# image_reject.net
KiCad netlist of a schematic drawn in Altium Designer
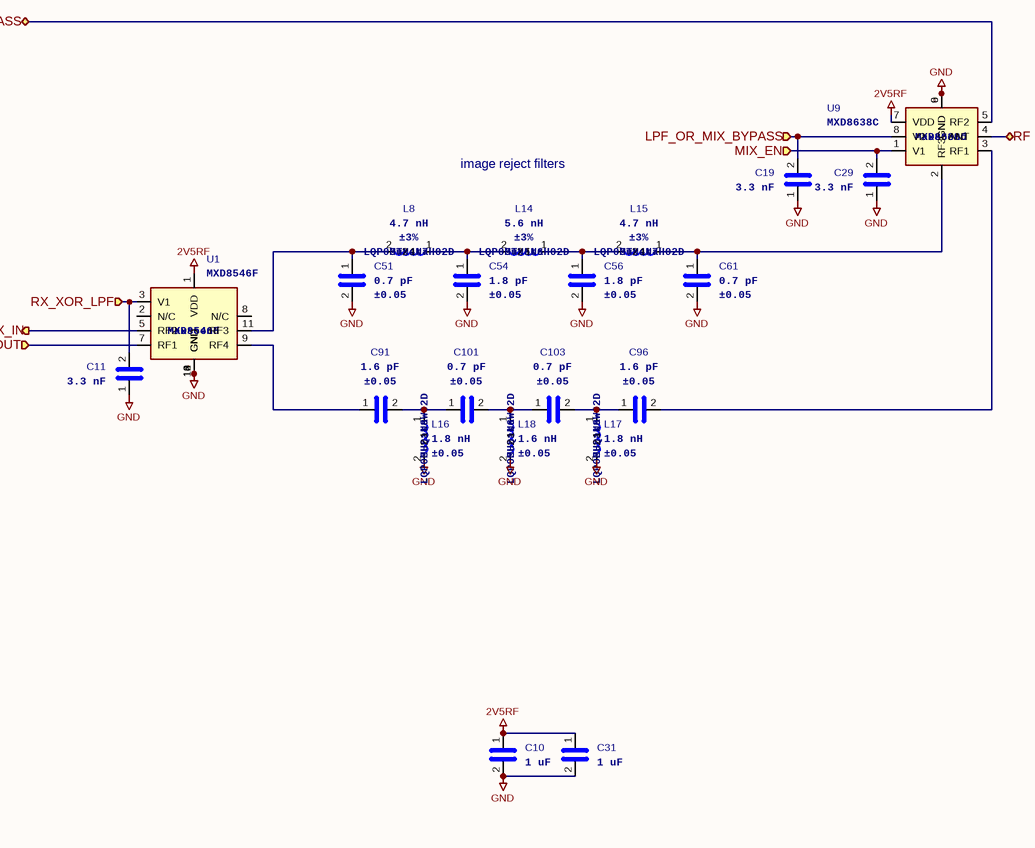
[diagram p0: image_reject.SchDoc]

(export (version "E")
  (design (tool "Eeschema 10.0.6"))
  (components
    (comp (ref "C10")
      (value "1 uF")
      (footprint "C_0201_0603Metric")
      (fields (field (name "MANUFACTURER") "Murata") (field (name "PART NUMBER") "GRM033R61A105ME44D"))
      (libsource (lib "Device") (part "C"))
    )
    (comp (ref "C11")
      (value "3.3 nF")
      (footprint "C_0201_0603Metric")
      (fields (field (name "MANUFACTURER") "Murata") (field (name "PART NUMBER") "GRM033R71A332KA01D"))
      (libsource (lib "Device") (part "C"))
    )
    (comp (ref "C19")
      (value "3.3 nF")
      (footprint "C_0201_0603Metric")
      (fields (field (name "MANUFACTURER") "Murata") (field (name "PART NUMBER") "GRM033R71A332KA01D"))
      (libsource (lib "Device") (part "C"))
    )
    (comp (ref "C29")
      (value "3.3 nF")
      (footprint "C_0201_0603Metric")
      (fields (field (name "MANUFACTURER") "Murata") (field (name "PART NUMBER") "GRM033R71A332KA01D"))
      (libsource (lib "Device") (part "C"))
    )
    (comp (ref "C31")
      (value "1 uF")
      (footprint "C_0201_0603Metric")
      (fields (field (name "MANUFACTURER") "Murata") (field (name "PART NUMBER") "GRM033R61A105ME44D"))
      (libsource (lib "Device") (part "C"))
    )
    (comp (ref "C51")
      (value "0.7 pF")
      (footprint "C_0201_0603Metric")
      (fields
        (field (name "MANUFACTURER") "Murata")
        (field (name "PART NUMBER") "GRM0335C1ER70WA01D")
        (field (name "TOLERANCE") "±0.05")
      )
      (libsource (lib "Device") (part "C"))
    )
    (comp (ref "C54")
      (value "1.8 pF")
      (footprint "C_0201_0603Metric")
      (fields
        (field (name "MANUFACTURER") "Murata")
        (field (name "PART NUMBER") "GRM0335C1E1R8WA01D")
        (field (name "TOLERANCE") "±0.05")
      )
      (libsource (lib "Device") (part "C"))
    )
    (comp (ref "C56")
      (value "1.8 pF")
      (footprint "C_0201_0603Metric")
      (fields
        (field (name "MANUFACTURER") "Murata")
        (field (name "PART NUMBER") "GRM0335C1E1R8WA01D")
        (field (name "TOLERANCE") "±0.05")
      )
      (libsource (lib "Device") (part "C"))
    )
    (comp (ref "C61")
      (value "0.7 pF")
      (footprint "C_0201_0603Metric")
      (fields
        (field (name "MANUFACTURER") "Murata")
        (field (name "PART NUMBER") "GRM0335C1ER70WA01D")
        (field (name "TOLERANCE") "±0.05")
      )
      (libsource (lib "Device") (part "C"))
    )
    (comp (ref "C91")
      (value "1.6 pF")
      (footprint "C_0201_0603Metric")
      (fields
        (field (name "MANUFACTURER") "Murata")
        (field (name "PART NUMBER") "GRM0335C1E1R6WA01D")
        (field (name "TOLERANCE") "±0.05")
      )
      (libsource (lib "Device") (part "C"))
    )
    (comp (ref "C96")
      (value "1.6 pF")
      (footprint "C_0201_0603Metric")
      (fields
        (field (name "MANUFACTURER") "Murata")
        (field (name "PART NUMBER") "GRM0335C1E1R6WA01D")
        (field (name "TOLERANCE") "±0.05")
      )
      (libsource (lib "Device") (part "C"))
    )
    (comp (ref "C101")
      (value "0.7 pF")
      (footprint "C_0201_0603Metric")
      (fields
        (field (name "MANUFACTURER") "Murata")
        (field (name "PART NUMBER") "GRM0335C1ER70WA01D")
        (field (name "TOLERANCE") "±0.05")
      )
      (libsource (lib "Device") (part "C"))
    )
    (comp (ref "C103")
      (value "0.7 pF")
      (footprint "C_0201_0603Metric")
      (fields
        (field (name "MANUFACTURER") "Murata")
        (field (name "PART NUMBER") "GRM0335C1ER70WA01D")
        (field (name "TOLERANCE") "±0.05")
      )
      (libsource (lib "Device") (part "C"))
    )
    (comp (ref "L8")
      (value "4.7 nH")
      (footprint "L_0201_0603Metric")
      (fields
        (field (name "MANUFACTURER") "Murata")
        (field (name "PART NUMBER") "LQP03TN4N7H02D")
        (field (name "TOLERANCE") "±3%")
      )
      (libsource (lib "Device") (part "L"))
    )
    (comp (ref "L14")
      (value "5.6 nH")
      (footprint "L_0201_0603Metric")
      (fields
        (field (name "MANUFACTURER") "Murata")
        (field (name "PART NUMBER") "LQP03TN5N6H02D")
        (field (name "TOLERANCE") "±3%")
      )
      (libsource (lib "Device") (part "L"))
    )
    (comp (ref "L15")
      (value "4.7 nH")
      (footprint "L_0201_0603Metric")
      (fields
        (field (name "MANUFACTURER") "Murata")
        (field (name "PART NUMBER") "LQP03TN4N7H02D")
        (field (name "TOLERANCE") "±3%")
      )
      (libsource (lib "Device") (part "L"))
    )
    (comp (ref "L16")
      (value "1.8 nH")
      (footprint "L_0201_0603Metric")
      (fields
        (field (name "MANUFACTURER") "Murata")
        (field (name "PART NUMBER") "LQP03HQ1N8W02D")
        (field (name "TOLERANCE") "±0.05")
      )
      (libsource (lib "Device") (part "L"))
    )
    (comp (ref "L17")
      (value "1.8 nH")
      (footprint "L_0201_0603Metric")
      (fields
        (field (name "MANUFACTURER") "Murata")
        (field (name "PART NUMBER") "LQP03HQ1N8W02D")
        (field (name "TOLERANCE") "±0.05")
      )
      (libsource (lib "Device") (part "L"))
    )
    (comp (ref "L18")
      (value "1.6 nH")
      (footprint "L_0201_0603Metric")
      (fields
        (field (name "MANUFACTURER") "Murata")
        (field (name "PART NUMBER") "LQP03HQ1N6W02D")
        (field (name "TOLERANCE") "±0.05")
      )
      (libsource (lib "Device") (part "L"))
    )
    (comp (ref "U1")
      (value "MXD8546F")
      (footprint "QFN-12-1EP_2x2mm_P0.5mm_EP1x1mm")
      (fields (field (name "MANUFACTURER") "Maxscend") (field (name "PART NUMBER") "MXD8546F"))
      (libsource (lib "praline") (part "MXD8546F"))
    )
    (comp (ref "U9")
      (value "MXD8638C")
      (footprint "MXD8638C")
      (fields (field (name "MANUFACTURER") "Maxscend") (field (name "PART NUMBER") "MXD8638C"))
      (libsource (lib "praline") (part "MXD8638"))
    )
  )
  (nets
    (net (code "1") (name "/LPF_OR_MIX_BYPASS") (class "Default")
      (node (ref "C19") (pin "2") (pinfunction "2_2") (pintype "passive"))
      (node (ref "U9") (pin "8") (pinfunction "V2_8") (pintype "passive"))
    )
    (net (code "2") (name "/MIX_BYPASS") (class "Default")
      (node (ref "U9") (pin "5") (pinfunction "RF2_5") (pintype "passive"))
    )
    (net (code "3") (name "/MIX_EN") (class "Default")
      (node (ref "C29") (pin "2") (pinfunction "2_2") (pintype "passive"))
      (node (ref "U9") (pin "1") (pinfunction "V1_1") (pintype "passive"))
    )
    (net (code "4") (name "/RF") (class "Default")
      (node (ref "U9") (pin "4") (pinfunction "ANT_4") (pintype "passive"))
    )
    (net (code "5") (name "/RX_MIX_IN") (class "Default")
      (node (ref "U1") (pin "5") (pinfunction "RF2_5") (pintype "passive"))
    )
    (net (code "6") (name "/RX_XOR_LPF") (class "Default")
      (node (ref "C11") (pin "2") (pinfunction "2_2") (pintype "passive"))
      (node (ref "U1") (pin "3") (pinfunction "V1_3") (pintype "passive"))
    )
    (net (code "7") (name "/TX_MIX_OUT") (class "Default")
      (node (ref "U1") (pin "7") (pinfunction "RF1_7") (pintype "passive"))
    )
    (net (code "8") (name "2V5RF") (class "Default")
      (node (ref "C10") (pin "1") (pinfunction "1_1") (pintype "passive"))
      (node (ref "C31") (pin "1") (pinfunction "1_1") (pintype "passive"))
      (node (ref "U1") (pin "1") (pinfunction "VDD_1") (pintype "passive"))
      (node (ref "U9") (pin "7") (pinfunction "VDD_7") (pintype "passive"))
    )
    (net (code "9") (name "GND") (class "Default")
      (node (ref "C10") (pin "2") (pinfunction "2_2") (pintype "passive"))
      (node (ref "C11") (pin "1") (pinfunction "1_1") (pintype "passive"))
      (node (ref "C19") (pin "1") (pinfunction "1_1") (pintype "passive"))
      (node (ref "C29") (pin "1") (pinfunction "1_1") (pintype "passive"))
      (node (ref "C31") (pin "2") (pinfunction "2_2") (pintype "passive"))
      (node (ref "C51") (pin "2") (pinfunction "2_2") (pintype "passive"))
      (node (ref "C54") (pin "2") (pinfunction "2_2") (pintype "passive"))
      (node (ref "C56") (pin "2") (pinfunction "2_2") (pintype "passive"))
      (node (ref "C61") (pin "2") (pinfunction "2_2") (pintype "passive"))
      (node (ref "L16") (pin "2") (pinfunction "2_2") (pintype "passive"))
      (node (ref "L17") (pin "2") (pinfunction "2_2") (pintype "passive"))
      (node (ref "L18") (pin "2") (pinfunction "2_2") (pintype "passive"))
      (node (ref "U1") (pin "10") (pinfunction "GND_10") (pintype "passive"))
      (node (ref "U1") (pin "12") (pinfunction "GND_12") (pintype "passive"))
      (node (ref "U1") (pin "13") (pinfunction "GND_13") (pintype "passive"))
      (node (ref "U1") (pin "4") (pinfunction "GND_4") (pintype "passive"))
      (node (ref "U1") (pin "6") (pinfunction "GND_6") (pintype "passive"))
      (node (ref "U9") (pin "6") (pinfunction "GND_6") (pintype "passive"))
      (node (ref "U9") (pin "9") (pinfunction "GND_9") (pintype "passive"))
    )
    (net (code "10") (name "Net-(C54-Pad1)") (class "Default")
      (node (ref "C54") (pin "1") (pinfunction "1_1") (pintype "passive"))
      (node (ref "L14") (pin "2") (pinfunction "2_2") (pintype "passive"))
      (node (ref "L8") (pin "1") (pinfunction "1_1") (pintype "passive"))
    )
    (net (code "11") (name "Net-(C56-Pad1)") (class "Default")
      (node (ref "C56") (pin "1") (pinfunction "1_1") (pintype "passive"))
      (node (ref "L14") (pin "1") (pinfunction "1_1") (pintype "passive"))
      (node (ref "L15") (pin "2") (pinfunction "2_2") (pintype "passive"))
    )
    (net (code "12") (name "Net-(C101-Pad1)") (class "Default")
      (node (ref "C101") (pin "1") (pinfunction "1_1") (pintype "passive"))
      (node (ref "C91") (pin "2") (pinfunction "2_2") (pintype "passive"))
      (node (ref "L16") (pin "1") (pinfunction "1_1") (pintype "passive"))
    )
    (net (code "13") (name "Net-(C101-Pad2)") (class "Default")
      (node (ref "C101") (pin "2") (pinfunction "2_2") (pintype "passive"))
      (node (ref "C103") (pin "1") (pinfunction "1_1") (pintype "passive"))
      (node (ref "L18") (pin "1") (pinfunction "1_1") (pintype "passive"))
    )
    (net (code "14") (name "Net-(C103-Pad2)") (class "Default")
      (node (ref "C103") (pin "2") (pinfunction "2_2") (pintype "passive"))
      (node (ref "C96") (pin "1") (pinfunction "1_1") (pintype "passive"))
      (node (ref "L17") (pin "1") (pinfunction "1_1") (pintype "passive"))
    )
    (net (code "15") (name "Net-(U1-RF3)") (class "Default")
      (node (ref "C51") (pin "1") (pinfunction "1_1") (pintype "passive"))
      (node (ref "L8") (pin "2") (pinfunction "2_2") (pintype "passive"))
      (node (ref "U1") (pin "11") (pinfunction "RF3_11") (pintype "passive"))
    )
    (net (code "16") (name "Net-(U1-RF4)") (class "Default")
      (node (ref "C91") (pin "1") (pinfunction "1_1") (pintype "passive"))
      (node (ref "U1") (pin "9") (pinfunction "RF4_9") (pintype "passive"))
    )
    (net (code "17") (name "Net-(U9-RF1)") (class "Default")
      (node (ref "C96") (pin "2") (pinfunction "2_2") (pintype "passive"))
      (node (ref "U9") (pin "3") (pinfunction "RF1_3") (pintype "passive"))
    )
    (net (code "18") (name "Net-(U9-RF3)") (class "Default")
      (node (ref "C61") (pin "1") (pinfunction "1_1") (pintype "passive"))
      (node (ref "L15") (pin "1") (pinfunction "1_1") (pintype "passive"))
      (node (ref "U9") (pin "2") (pinfunction "RF3_2") (pintype "passive"))
    )
    (net (code "19") (name "unconnected-(U1-N{slash}C-Pad2)") (class "Default")
      (node (ref "U1") (pin "2") (pinfunction "N/C_2") (pintype "passive"))
    )
    (net (code "20") (name "unconnected-(U1-N{slash}C-Pad8)") (class "Default")
      (node (ref "U1") (pin "8") (pinfunction "N/C_8") (pintype "passive"))
    )
  )
)
